# bristol_longshot.net
KiCad netlist of a schematic drawn in EAGLE
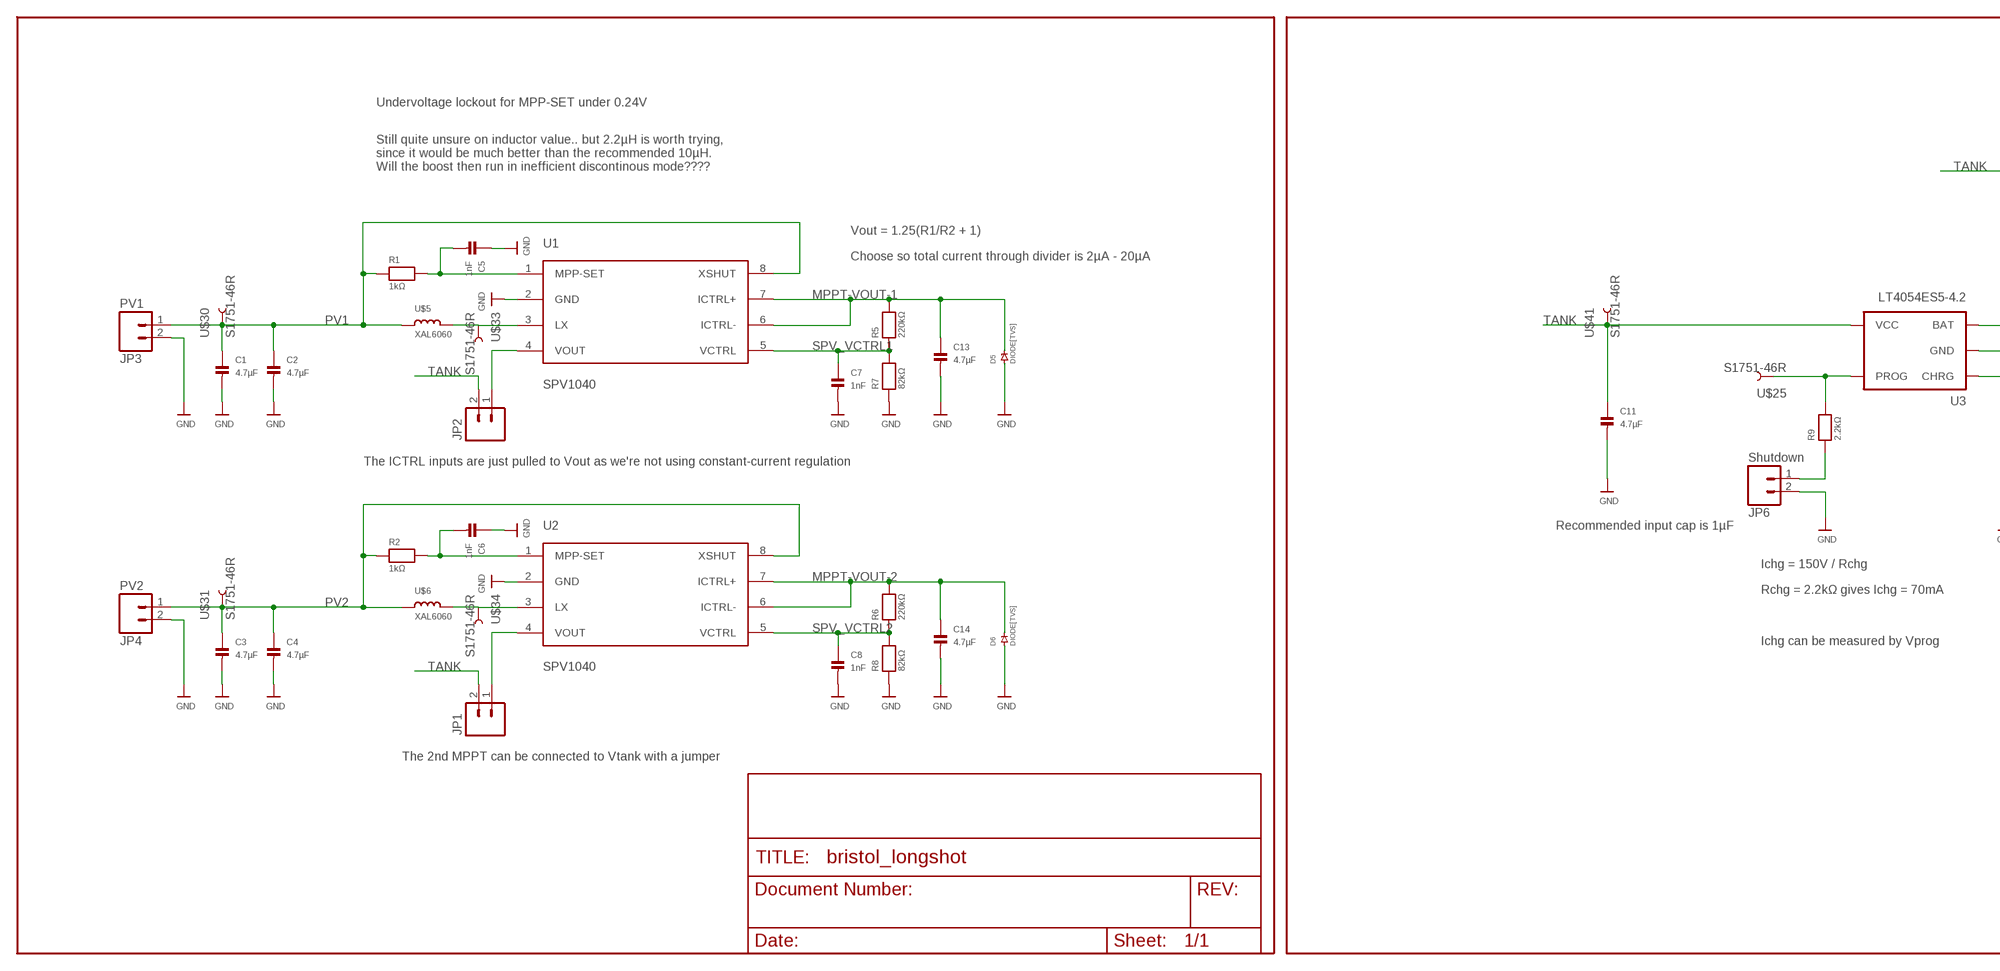
[diagram p0: schematic, sheet 1, part 1 of 2]
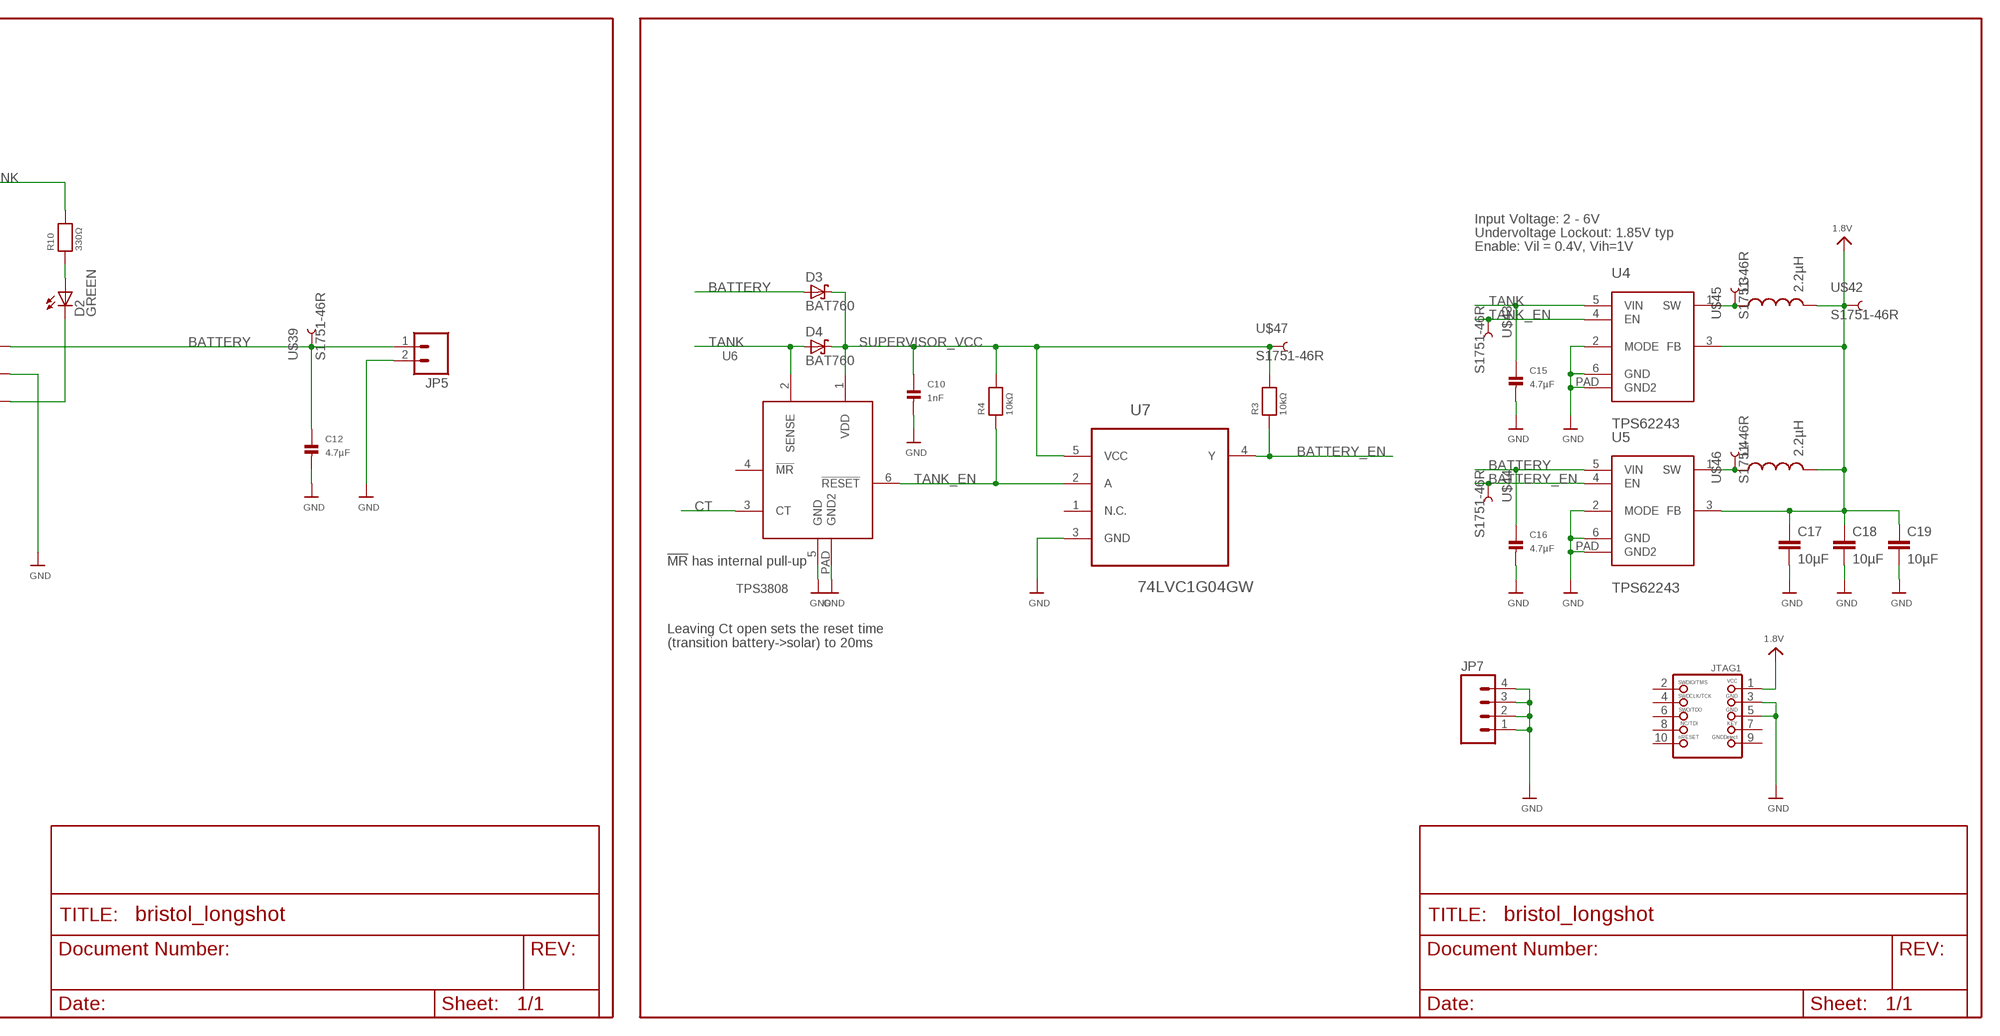
[diagram p1: schematic, sheet 1, part 2 of 2]

(export (version "E")
  (design (tool "Eeschema 10.0.6"))
  (components
    (comp (ref "C1")
      (value "4.7µF")
      (footprint "eagle-import:_0402")
      (libsource (lib "eagle-import") (part "CAP_CERAMIC_0402"))
    )
    (comp (ref "C2")
      (value "4.7µF")
      (footprint "eagle-import:_0402")
      (libsource (lib "eagle-import") (part "CAP_CERAMIC_0402"))
    )
    (comp (ref "C3")
      (value "4.7µF")
      (footprint "eagle-import:_0402")
      (libsource (lib "eagle-import") (part "CAP_CERAMIC_0402"))
    )
    (comp (ref "C4")
      (value "4.7µF")
      (footprint "eagle-import:_0402")
      (libsource (lib "eagle-import") (part "CAP_CERAMIC_0402"))
    )
    (comp (ref "C5")
      (value "1nF")
      (footprint "eagle-import:_0402")
      (libsource (lib "eagle-import") (part "CAP_CERAMIC_0402"))
    )
    (comp (ref "C6")
      (value "1nF")
      (footprint "eagle-import:_0402")
      (libsource (lib "eagle-import") (part "CAP_CERAMIC_0402"))
    )
    (comp (ref "C7")
      (value "1nF")
      (footprint "eagle-import:_0402")
      (libsource (lib "eagle-import") (part "CAP_CERAMIC_0402"))
    )
    (comp (ref "C8")
      (value "1nF")
      (footprint "eagle-import:_0402")
      (libsource (lib "eagle-import") (part "CAP_CERAMIC_0402"))
    )
    (comp (ref "C10")
      (value "1nF")
      (footprint "eagle-import:_0402")
      (libsource (lib "eagle-import") (part "CAP_CERAMIC_0402"))
    )
    (comp (ref "C11")
      (value "4.7µF")
      (footprint "eagle-import:_0402")
      (libsource (lib "eagle-import") (part "CAP_CERAMIC_0402"))
    )
    (comp (ref "C12")
      (value "4.7µF")
      (footprint "eagle-import:_0402")
      (libsource (lib "eagle-import") (part "CAP_CERAMIC_0402"))
    )
    (comp (ref "C13")
      (value "4.7µF")
      (footprint "eagle-import:_0402")
      (libsource (lib "eagle-import") (part "CAP_CERAMIC_0402"))
    )
    (comp (ref "C14")
      (value "4.7µF")
      (footprint "eagle-import:_0402")
      (libsource (lib "eagle-import") (part "CAP_CERAMIC_0402"))
    )
    (comp (ref "C15")
      (value "4.7µF")
      (footprint "eagle-import:_0402")
      (libsource (lib "eagle-import") (part "CAP_CERAMIC_0402"))
    )
    (comp (ref "C16")
      (value "4.7µF")
      (footprint "eagle-import:_0402")
      (libsource (lib "eagle-import") (part "CAP_CERAMIC_0402"))
    )
    (comp (ref "C17")
      (value "10µF")
      (footprint "eagle-import:C0603K")
      (libsource (lib "eagle-import") (part "C-EUC0603K"))
    )
    (comp (ref "C18")
      (value "10µF")
      (footprint "eagle-import:C0603K")
      (libsource (lib "eagle-import") (part "C-EUC0603K"))
    )
    (comp (ref "C19")
      (value "10µF")
      (footprint "eagle-import:C0603K")
      (libsource (lib "eagle-import") (part "C-EUC0603K"))
    )
    (comp (ref "D2")
      (value "GREEN")
      (footprint "eagle-import:CHIPLED_0603")
      (libsource (lib "eagle-import") (part "LEDCHIPLED_0603"))
    )
    (comp (ref "D3")
      (value "BAT760")
      (footprint "eagle-import:SOD323")
      (libsource (lib "eagle-import") (part "BAT760"))
    )
    (comp (ref "D4")
      (value "BAT760")
      (footprint "eagle-import:SOD323")
      (libsource (lib "eagle-import") (part "BAT760"))
    )
    (comp (ref "D5")
      (value "DIODE[TVS]")
      (footprint "eagle-import:SOD123W")
      (libsource (lib "eagle-import") (part "DIODE[TVS]"))
    )
    (comp (ref "D6")
      (value "DIODE[TVS]")
      (footprint "eagle-import:SOD123W")
      (libsource (lib "eagle-import") (part "DIODE[TVS]"))
    )
    (comp (ref "JP1")
      (value "M02LOCK")
      (footprint "eagle-import:1X02_LOCK")
      (libsource (lib "eagle-import") (part "M02LOCK"))
    )
    (comp (ref "JP2")
      (value "M02LOCK")
      (footprint "eagle-import:1X02_LOCK")
      (libsource (lib "eagle-import") (part "M02LOCK"))
    )
    (comp (ref "JP3")
      (value "PV1")
      (footprint "eagle-import:SCREWTERMINAL-3.5MM-2_LOCK")
      (libsource (lib "eagle-import") (part "M023.5MM_LOCK"))
    )
    (comp (ref "JP4")
      (value "PV2")
      (footprint "eagle-import:SCREWTERMINAL-3.5MM-2_LOCK")
      (libsource (lib "eagle-import") (part "M023.5MM_LOCK"))
    )
    (comp (ref "JP5")
      (value "M023.5MM_LOCK")
      (footprint "eagle-import:SCREWTERMINAL-3.5MM-2_LOCK")
      (libsource (lib "eagle-import") (part "M023.5MM_LOCK"))
    )
    (comp (ref "JP6")
      (value "Shutdown")
      (footprint "eagle-import:1X02_LOCK")
      (libsource (lib "eagle-import") (part "M02LOCK"))
    )
    (comp (ref "JP7")
      (value "M04LOCK")
      (footprint "eagle-import:1X04_LOCK")
      (libsource (lib "eagle-import") (part "M04LOCK"))
    )
    (comp (ref "JTAG1")
      (value "JTAG-CORTEXM3SMT")
      (footprint "eagle-import:2X05_1.27MM_SMT")
      (libsource (lib "eagle-import") (part "JTAG-CORTEXM3SMT"))
    )
    (comp (ref "L3")
      (value "2.2µH")
      (footprint "eagle-import:1007")
      (libsource (lib "eagle-import") (part "INDUCTOR1007"))
    )
    (comp (ref "L4")
      (value "2.2µH")
      (footprint "eagle-import:1007")
      (libsource (lib "eagle-import") (part "INDUCTOR1007"))
    )
    (comp (ref "R1")
      (value "1kΩ")
      (footprint "eagle-import:_0402")
      (libsource (lib "eagle-import") (part "RESISTOR_0402"))
    )
    (comp (ref "R2")
      (value "1kΩ")
      (footprint "eagle-import:_0402")
      (libsource (lib "eagle-import") (part "RESISTOR_0402"))
    )
    (comp (ref "R3")
      (value "10kΩ")
      (footprint "eagle-import:_0402")
      (libsource (lib "eagle-import") (part "RESISTOR_0402"))
    )
    (comp (ref "R4")
      (value "10kΩ")
      (footprint "eagle-import:_0402")
      (libsource (lib "eagle-import") (part "RESISTOR_0402"))
    )
    (comp (ref "R5")
      (value "220kΩ")
      (footprint "eagle-import:_0402")
      (libsource (lib "eagle-import") (part "RESISTOR_0402"))
    )
    (comp (ref "R6")
      (value "220kΩ")
      (footprint "eagle-import:_0402")
      (libsource (lib "eagle-import") (part "RESISTOR_0402"))
    )
    (comp (ref "R7")
      (value "82kΩ")
      (footprint "eagle-import:_0402")
      (libsource (lib "eagle-import") (part "RESISTOR_0402"))
    )
    (comp (ref "R8")
      (value "82kΩ")
      (footprint "eagle-import:_0402")
      (libsource (lib "eagle-import") (part "RESISTOR_0402"))
    )
    (comp (ref "R9")
      (value "2.2kΩ")
      (footprint "eagle-import:_0402")
      (libsource (lib "eagle-import") (part "RESISTOR_0402"))
    )
    (comp (ref "R10")
      (value "330Ω")
      (footprint "eagle-import:_0402")
      (libsource (lib "eagle-import") (part "RESISTOR_0402"))
    )
    (comp (ref "U$5")
      (value "XAL6060")
      (footprint "eagle-import:XAL60")
      (libsource (lib "eagle-import") (part "XAL6060"))
    )
    (comp (ref "U$6")
      (value "XAL6060")
      (footprint "eagle-import:XAL60")
      (libsource (lib "eagle-import") (part "XAL6060"))
    )
    (comp (ref "U$25")
      (value "S1751-46R")
      (footprint "eagle-import:S1751-46R")
      (libsource (lib "eagle-import") (part "S1751-46R"))
    )
    (comp (ref "U$30")
      (value "S1751-46R")
      (footprint "eagle-import:S1751-46R")
      (libsource (lib "eagle-import") (part "S1751-46R"))
    )
    (comp (ref "U$31")
      (value "S1751-46R")
      (footprint "eagle-import:S1751-46R")
      (libsource (lib "eagle-import") (part "S1751-46R"))
    )
    (comp (ref "U$33")
      (value "S1751-46R")
      (footprint "eagle-import:S1751-46R")
      (libsource (lib "eagle-import") (part "S1751-46R"))
    )
    (comp (ref "U$34")
      (value "S1751-46R")
      (footprint "eagle-import:S1751-46R")
      (libsource (lib "eagle-import") (part "S1751-46R"))
    )
    (comp (ref "U$39")
      (value "S1751-46R")
      (footprint "eagle-import:S1751-46R")
      (libsource (lib "eagle-import") (part "S1751-46R"))
    )
    (comp (ref "U$41")
      (value "S1751-46R")
      (footprint "eagle-import:S1751-46R")
      (libsource (lib "eagle-import") (part "S1751-46R"))
    )
    (comp (ref "U$42")
      (value "S1751-46R")
      (footprint "eagle-import:S1751-46R")
      (libsource (lib "eagle-import") (part "S1751-46R"))
    )
    (comp (ref "U$43")
      (value "S1751-46R")
      (footprint "eagle-import:S1751-46R")
      (libsource (lib "eagle-import") (part "S1751-46R"))
    )
    (comp (ref "U$44")
      (value "S1751-46R")
      (footprint "eagle-import:S1751-46R")
      (libsource (lib "eagle-import") (part "S1751-46R"))
    )
    (comp (ref "U$45")
      (value "S1751-46R")
      (footprint "eagle-import:S1751-46R")
      (libsource (lib "eagle-import") (part "S1751-46R"))
    )
    (comp (ref "U$46")
      (value "S1751-46R")
      (footprint "eagle-import:S1751-46R")
      (libsource (lib "eagle-import") (part "S1751-46R"))
    )
    (comp (ref "U$47")
      (value "S1751-46R")
      (footprint "eagle-import:S1751-46R")
      (libsource (lib "eagle-import") (part "S1751-46R"))
    )
    (comp (ref "U1")
      (value "SPV1040")
      (footprint "eagle-import:TSSOP8")
      (libsource (lib "eagle-import") (part "SPV1040"))
    )
    (comp (ref "U2")
      (value "SPV1040")
      (footprint "eagle-import:TSSOP8")
      (libsource (lib "eagle-import") (part "SPV1040"))
    )
    (comp (ref "U3")
      (value "LT4054ES5-4.2")
      (footprint "eagle-import:SOT23-5")
      (libsource (lib "eagle-import") (part "LT4054ES5-4.2"))
    )
    (comp (ref "U4")
      (value "TPS62243")
      (footprint "eagle-import:S-PWSON-N6")
      (libsource (lib "eagle-import") (part "TPS62243"))
    )
    (comp (ref "U5")
      (value "TPS62243")
      (footprint "eagle-import:S-PWSON-N6")
      (libsource (lib "eagle-import") (part "TPS62243"))
    )
    (comp (ref "U6")
      (value "TPS3808")
      (footprint "eagle-import:S-PWSON-N6")
      (libsource (lib "eagle-import") (part "TPS3808"))
    )
    (comp (ref "U7")
      (value "74LVC1G04GW")
      (footprint "eagle-import:SOT65P210X110-5N")
      (libsource (lib "eagle-import") (part "74LVC1G04GW"))
    )
  )
  (nets
    (net (code "1") (name "/BATTERY") (class "Default")
      (node (ref "C12") (pin "1") (pinfunction "P$1_1") (pintype "passive"))
      (node (ref "C16") (pin "1") (pinfunction "P$1_1") (pintype "passive"))
      (node (ref "D3") (pin "A") (pinfunction "A_A") (pintype "passive"))
      (node (ref "JP5") (pin "1") (pinfunction "1_1") (pintype "passive"))
      (node (ref "U$39") (pin "PAD") (pinfunction "1_PAD") (pintype "bidirectional"))
      (node (ref "U3") (pin "3") (pinfunction "BAT_3") (pintype "input"))
      (node (ref "U5") (pin "5") (pinfunction "VIN_5") (pintype "bidirectional"))
    )
    (net (code "2") (name "/BATTERY_EN") (class "Default")
      (node (ref "R3") (pin "1") (pinfunction "1_1") (pintype "passive"))
      (node (ref "U$44") (pin "PAD") (pinfunction "1_PAD") (pintype "bidirectional"))
      (node (ref "U5") (pin "4") (pinfunction "EN_4") (pintype "bidirectional"))
      (node (ref "U7") (pin "4") (pinfunction "Y_4") (pintype "output"))
    )
    (net (code "3") (name "/CT") (class "Default")
      (node (ref "U6") (pin "3") (pinfunction "CT_3") (pintype "bidirectional"))
    )
    (net (code "4") (name "/MPPT-VOUT-1") (class "Default")
      (node (ref "C13") (pin "1") (pinfunction "P$1_1") (pintype "passive"))
      (node (ref "D5") (pin "P$2") (pinfunction "2_P$2") (pintype "bidirectional"))
      (node (ref "JP2") (pin "1") (pinfunction "1_1") (pintype "passive"))
      (node (ref "R5") (pin "2") (pinfunction "2_2") (pintype "passive"))
      (node (ref "U1") (pin "4") (pinfunction "VOUT_4") (pintype "bidirectional"))
      (node (ref "U1") (pin "6") (pinfunction "ICTRL-_6") (pintype "bidirectional"))
      (node (ref "U1") (pin "7") (pinfunction "ICTRL+_7") (pintype "bidirectional"))
    )
    (net (code "5") (name "/MPPT-VOUT-2") (class "Default")
      (node (ref "C14") (pin "1") (pinfunction "P$1_1") (pintype "passive"))
      (node (ref "D6") (pin "P$2") (pinfunction "2_P$2") (pintype "bidirectional"))
      (node (ref "JP1") (pin "1") (pinfunction "1_1") (pintype "passive"))
      (node (ref "R6") (pin "2") (pinfunction "2_2") (pintype "passive"))
      (node (ref "U2") (pin "4") (pinfunction "VOUT_4") (pintype "bidirectional"))
      (node (ref "U2") (pin "6") (pinfunction "ICTRL-_6") (pintype "bidirectional"))
      (node (ref "U2") (pin "7") (pinfunction "ICTRL+_7") (pintype "bidirectional"))
    )
    (net (code "6") (name "/PV1") (class "Default")
      (node (ref "C1") (pin "1") (pinfunction "P$1_1") (pintype "passive"))
      (node (ref "C2") (pin "1") (pinfunction "P$1_1") (pintype "passive"))
      (node (ref "JP3") (pin "1") (pinfunction "1_1") (pintype "passive"))
      (node (ref "R1") (pin "1") (pinfunction "1_1") (pintype "passive"))
      (node (ref "U$30") (pin "PAD") (pinfunction "1_PAD") (pintype "bidirectional"))
      (node (ref "U$5") (pin "P$1") (pinfunction "1_P$1") (pintype "passive"))
      (node (ref "U1") (pin "8") (pinfunction "XSHUT_8") (pintype "bidirectional"))
    )
    (net (code "7") (name "/PV2") (class "Default")
      (node (ref "C3") (pin "1") (pinfunction "P$1_1") (pintype "passive"))
      (node (ref "C4") (pin "1") (pinfunction "P$1_1") (pintype "passive"))
      (node (ref "JP4") (pin "1") (pinfunction "1_1") (pintype "passive"))
      (node (ref "R2") (pin "1") (pinfunction "1_1") (pintype "passive"))
      (node (ref "U$31") (pin "PAD") (pinfunction "1_PAD") (pintype "bidirectional"))
      (node (ref "U$6") (pin "P$1") (pinfunction "1_P$1") (pintype "passive"))
      (node (ref "U2") (pin "8") (pinfunction "XSHUT_8") (pintype "bidirectional"))
    )
    (net (code "8") (name "/SPV_VCTRL1") (class "Default")
      (node (ref "C7") (pin "1") (pinfunction "P$1_1") (pintype "passive"))
      (node (ref "R5") (pin "1") (pinfunction "1_1") (pintype "passive"))
      (node (ref "R7") (pin "2") (pinfunction "2_2") (pintype "passive"))
      (node (ref "U1") (pin "5") (pinfunction "VCTRL_5") (pintype "bidirectional"))
    )
    (net (code "9") (name "/SPV_VCTRL2") (class "Default")
      (node (ref "C8") (pin "1") (pinfunction "P$1_1") (pintype "passive"))
      (node (ref "R6") (pin "1") (pinfunction "1_1") (pintype "passive"))
      (node (ref "R8") (pin "2") (pinfunction "2_2") (pintype "passive"))
      (node (ref "U2") (pin "5") (pinfunction "VCTRL_5") (pintype "bidirectional"))
    )
    (net (code "10") (name "/SUPERVISOR_VCC") (class "Default")
      (node (ref "C10") (pin "1") (pinfunction "P$1_1") (pintype "passive"))
      (node (ref "D3") (pin "C") (pinfunction "C_C") (pintype "passive"))
      (node (ref "D4") (pin "C") (pinfunction "C_C") (pintype "passive"))
      (node (ref "R3") (pin "2") (pinfunction "2_2") (pintype "passive"))
      (node (ref "R4") (pin "2") (pinfunction "2_2") (pintype "passive"))
      (node (ref "U$47") (pin "PAD") (pinfunction "1_PAD") (pintype "bidirectional"))
      (node (ref "U6") (pin "1") (pinfunction "VDD_1") (pintype "bidirectional"))
      (node (ref "U7") (pin "5") (pinfunction "VCC_5") (pintype "power_in"))
    )
    (net (code "11") (name "/TANK") (class "Default")
      (node (ref "C11") (pin "1") (pinfunction "P$1_1") (pintype "passive"))
      (node (ref "C15") (pin "1") (pinfunction "P$1_1") (pintype "passive"))
      (node (ref "D4") (pin "A") (pinfunction "A_A") (pintype "passive"))
      (node (ref "JP1") (pin "2") (pinfunction "2_2") (pintype "passive"))
      (node (ref "JP2") (pin "2") (pinfunction "2_2") (pintype "passive"))
      (node (ref "R10") (pin "2") (pinfunction "2_2") (pintype "passive"))
      (node (ref "U$41") (pin "PAD") (pinfunction "1_PAD") (pintype "bidirectional"))
      (node (ref "U3") (pin "4") (pinfunction "VCC_4") (pintype "input"))
      (node (ref "U4") (pin "5") (pinfunction "VIN_5") (pintype "bidirectional"))
      (node (ref "U6") (pin "2") (pinfunction "SENSE_2") (pintype "bidirectional"))
    )
    (net (code "12") (name "/TANK_EN") (class "Default")
      (node (ref "R4") (pin "1") (pinfunction "1_1") (pintype "passive"))
      (node (ref "U$43") (pin "PAD") (pinfunction "1_PAD") (pintype "bidirectional"))
      (node (ref "U4") (pin "4") (pinfunction "EN_4") (pintype "bidirectional"))
      (node (ref "U6") (pin "6") (pinfunction "~{RESET}_6") (pintype "bidirectional"))
      (node (ref "U7") (pin "2") (pinfunction "A_2") (pintype "input"))
    )
    (net (code "13") (name "1.8V") (class "Default")
      (node (ref "C17") (pin "1") (pinfunction "1_1") (pintype "passive"))
      (node (ref "C18") (pin "1") (pinfunction "1_1") (pintype "passive"))
      (node (ref "C19") (pin "1") (pinfunction "1_1") (pintype "passive"))
      (node (ref "JTAG1") (pin "1") (pinfunction "1_1") (pintype "passive"))
      (node (ref "L3") (pin "2") (pinfunction "2_2") (pintype "passive"))
      (node (ref "L4") (pin "2") (pinfunction "2_2") (pintype "passive"))
      (node (ref "U$42") (pin "PAD") (pinfunction "1_PAD") (pintype "bidirectional"))
      (node (ref "U4") (pin "3") (pinfunction "FB_3") (pintype "bidirectional"))
      (node (ref "U5") (pin "3") (pinfunction "FB_3") (pintype "bidirectional"))
    )
    (net (code "14") (name "GND") (class "Default")
      (node (ref "C1") (pin "2") (pinfunction "P$2_2") (pintype "passive"))
      (node (ref "C10") (pin "2") (pinfunction "P$2_2") (pintype "passive"))
      (node (ref "C11") (pin "2") (pinfunction "P$2_2") (pintype "passive"))
      (node (ref "C12") (pin "2") (pinfunction "P$2_2") (pintype "passive"))
      (node (ref "C13") (pin "2") (pinfunction "P$2_2") (pintype "passive"))
      (node (ref "C14") (pin "2") (pinfunction "P$2_2") (pintype "passive"))
      (node (ref "C15") (pin "2") (pinfunction "P$2_2") (pintype "passive"))
      (node (ref "C16") (pin "2") (pinfunction "P$2_2") (pintype "passive"))
      (node (ref "C17") (pin "2") (pinfunction "2_2") (pintype "passive"))
      (node (ref "C18") (pin "2") (pinfunction "2_2") (pintype "passive"))
      (node (ref "C19") (pin "2") (pinfunction "2_2") (pintype "passive"))
      (node (ref "C2") (pin "2") (pinfunction "P$2_2") (pintype "passive"))
      (node (ref "C3") (pin "2") (pinfunction "P$2_2") (pintype "passive"))
      (node (ref "C4") (pin "2") (pinfunction "P$2_2") (pintype "passive"))
      (node (ref "C5") (pin "1") (pinfunction "P$1_1") (pintype "passive"))
      (node (ref "C6") (pin "1") (pinfunction "P$1_1") (pintype "passive"))
      (node (ref "C7") (pin "2") (pinfunction "P$2_2") (pintype "passive"))
      (node (ref "C8") (pin "2") (pinfunction "P$2_2") (pintype "passive"))
      (node (ref "D5") (pin "P$1") (pinfunction "1_P$1") (pintype "bidirectional"))
      (node (ref "D6") (pin "P$1") (pinfunction "1_P$1") (pintype "bidirectional"))
      (node (ref "JP3") (pin "2") (pinfunction "2_2") (pintype "passive"))
      (node (ref "JP4") (pin "2") (pinfunction "2_2") (pintype "passive"))
      (node (ref "JP5") (pin "2") (pinfunction "2_2") (pintype "passive"))
      (node (ref "JP6") (pin "2") (pinfunction "2_2") (pintype "passive"))
      (node (ref "JP7") (pin "1") (pinfunction "1_1") (pintype "passive"))
      (node (ref "JP7") (pin "2") (pinfunction "2_2") (pintype "passive"))
      (node (ref "JP7") (pin "3") (pinfunction "3_3") (pintype "passive"))
      (node (ref "JP7") (pin "4") (pinfunction "4_4") (pintype "passive"))
      (node (ref "JTAG1") (pin "3") (pinfunction "3_3") (pintype "passive"))
      (node (ref "JTAG1") (pin "5") (pinfunction "5_5") (pintype "passive"))
      (node (ref "R7") (pin "1") (pinfunction "1_1") (pintype "passive"))
      (node (ref "R8") (pin "1") (pinfunction "1_1") (pintype "passive"))
      (node (ref "U1") (pin "2") (pinfunction "GND_2") (pintype "power_in"))
      (node (ref "U2") (pin "2") (pinfunction "GND_2") (pintype "power_in"))
      (node (ref "U3") (pin "2") (pinfunction "GND_2") (pintype "input"))
      (node (ref "U4") (pin "2") (pinfunction "MODE_2") (pintype "bidirectional"))
      (node (ref "U4") (pin "6") (pinfunction "GND_6") (pintype "bidirectional"))
      (node (ref "U4") (pin "PAD") (pinfunction "GND2_PAD") (pintype "bidirectional"))
      (node (ref "U5") (pin "2") (pinfunction "MODE_2") (pintype "bidirectional"))
      (node (ref "U5") (pin "6") (pinfunction "GND_6") (pintype "bidirectional"))
      (node (ref "U5") (pin "PAD") (pinfunction "GND2_PAD") (pintype "bidirectional"))
      (node (ref "U6") (pin "5") (pinfunction "GND_5") (pintype "bidirectional"))
      (node (ref "U6") (pin "PAD") (pinfunction "GND2_PAD") (pintype "bidirectional"))
      (node (ref "U7") (pin "3") (pinfunction "GND_3") (pintype "passive"))
    )
    (net (code "15") (name "Net-(C5-P$2)") (class "Default")
      (node (ref "C5") (pin "2") (pinfunction "P$2_2") (pintype "passive"))
      (node (ref "R1") (pin "2") (pinfunction "2_2") (pintype "passive"))
      (node (ref "U1") (pin "1") (pinfunction "MPP-SET_1") (pintype "bidirectional"))
    )
    (net (code "16") (name "Net-(C6-P$2)") (class "Default")
      (node (ref "C6") (pin "2") (pinfunction "P$2_2") (pintype "passive"))
      (node (ref "R2") (pin "2") (pinfunction "2_2") (pintype "passive"))
      (node (ref "U2") (pin "1") (pinfunction "MPP-SET_1") (pintype "bidirectional"))
    )
    (net (code "17") (name "Net-(D2-PadA)") (class "Default")
      (node (ref "D2") (pin "A") (pinfunction "A_A") (pintype "passive"))
      (node (ref "R10") (pin "1") (pinfunction "1_1") (pintype "passive"))
    )
    (net (code "18") (name "Net-(JP6-Pad1)") (class "Default")
      (node (ref "JP6") (pin "1") (pinfunction "1_1") (pintype "passive"))
      (node (ref "R9") (pin "1") (pinfunction "1_1") (pintype "passive"))
    )
    (net (code "19") (name "Net-(U$25-1)") (class "Default")
      (node (ref "R9") (pin "2") (pinfunction "2_2") (pintype "passive"))
      (node (ref "U$25") (pin "PAD") (pinfunction "1_PAD") (pintype "bidirectional"))
      (node (ref "U3") (pin "5") (pinfunction "PROG_5") (pintype "passive"))
    )
    (net (code "20") (name "Net-(U$33-1)") (class "Default")
      (node (ref "U$33") (pin "PAD") (pinfunction "1_PAD") (pintype "bidirectional"))
      (node (ref "U$5") (pin "P$2") (pinfunction "2_P$2") (pintype "passive"))
      (node (ref "U1") (pin "3") (pinfunction "LX_3") (pintype "bidirectional"))
    )
    (net (code "21") (name "Net-(U$34-1)") (class "Default")
      (node (ref "U$34") (pin "PAD") (pinfunction "1_PAD") (pintype "bidirectional"))
      (node (ref "U$6") (pin "P$2") (pinfunction "2_P$2") (pintype "passive"))
      (node (ref "U2") (pin "3") (pinfunction "LX_3") (pintype "bidirectional"))
    )
    (net (code "22") (name "Net-(U$45-1)") (class "Default")
      (node (ref "L3") (pin "1") (pinfunction "1_1") (pintype "passive"))
      (node (ref "U$45") (pin "PAD") (pinfunction "1_PAD") (pintype "bidirectional"))
      (node (ref "U4") (pin "1") (pinfunction "SW_1") (pintype "bidirectional"))
    )
    (net (code "23") (name "Net-(U$46-1)") (class "Default")
      (node (ref "L4") (pin "1") (pinfunction "1_1") (pintype "passive"))
      (node (ref "U$46") (pin "PAD") (pinfunction "1_PAD") (pintype "bidirectional"))
      (node (ref "U5") (pin "1") (pinfunction "SW_1") (pintype "bidirectional"))
    )
    (net (code "24") (name "Net-(U3-CHRG)") (class "Default")
      (node (ref "D2") (pin "C") (pinfunction "C_C") (pintype "passive"))
      (node (ref "U3") (pin "1") (pinfunction "CHRG_1") (pintype "input"))
    )
    (net (code "25") (name "unconnected-(JTAG1-Pad2)") (class "Default")
      (node (ref "JTAG1") (pin "2") (pinfunction "2_2") (pintype "passive"))
    )
    (net (code "26") (name "unconnected-(JTAG1-Pad4)") (class "Default")
      (node (ref "JTAG1") (pin "4") (pinfunction "4_4") (pintype "passive"))
    )
    (net (code "27") (name "unconnected-(JTAG1-Pad6)") (class "Default")
      (node (ref "JTAG1") (pin "6") (pinfunction "6_6") (pintype "passive"))
    )
    (net (code "28") (name "unconnected-(JTAG1-Pad7)") (class "Default")
      (node (ref "JTAG1") (pin "7") (pinfunction "7_7") (pintype "passive"))
    )
    (net (code "29") (name "unconnected-(JTAG1-Pad8)") (class "Default")
      (node (ref "JTAG1") (pin "8") (pinfunction "8_8") (pintype "passive"))
    )
    (net (code "30") (name "unconnected-(JTAG1-Pad9)") (class "Default")
      (node (ref "JTAG1") (pin "9") (pinfunction "9_9") (pintype "passive"))
    )
    (net (code "31") (name "unconnected-(JTAG1-Pad10)") (class "Default")
      (node (ref "JTAG1") (pin "10") (pinfunction "10_10") (pintype "passive"))
    )
    (net (code "32") (name "unconnected-(U6-~{MR}-Pad4)") (class "Default")
      (node (ref "U6") (pin "4") (pinfunction "~{MR}_4") (pintype "bidirectional"))
    )
    (net (code "33") (name "unconnected-(U7-N.C.-Pad1)") (class "Default")
      (node (ref "U7") (pin "1") (pinfunction "N.C._1") (pintype "no_connect"))
    )
  )
)
